# Ctrl_Joy.net
KiCad netlist of a schematic drawn in EAGLE
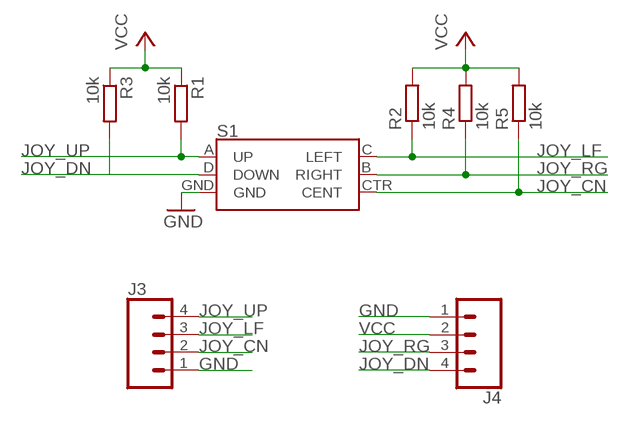
[diagram p0: schematic, sheet 1]

(export (version "E")
  (design (tool "Eeschema 10.0.6"))
  (components
    (comp (ref "J3")
      (value "CONN_04")
      (footprint "eagle-import:1X04")
      (libsource (lib "eagle-import") (part "CONN_04"))
    )
    (comp (ref "J4")
      (value "CONN_04")
      (footprint "eagle-import:1X04")
      (libsource (lib "eagle-import") (part "CONN_04"))
    )
    (comp (ref "R1")
      (value "10k")
      (footprint "eagle-import:R0603")
      (libsource (lib "eagle-import") (part "R-EU_R0603"))
    )
    (comp (ref "R2")
      (value "10k")
      (footprint "eagle-import:R0603")
      (libsource (lib "eagle-import") (part "R-EU_R0603"))
    )
    (comp (ref "R3")
      (value "10k")
      (footprint "eagle-import:R0603")
      (libsource (lib "eagle-import") (part "R-EU_R0603"))
    )
    (comp (ref "R4")
      (value "10k")
      (footprint "eagle-import:R0603")
      (libsource (lib "eagle-import") (part "R-EU_R0603"))
    )
    (comp (ref "R5")
      (value "10k")
      (footprint "eagle-import:R0603")
      (libsource (lib "eagle-import") (part "R-EU_R0603"))
    )
    (comp (ref "S1")
      (value "JOYSTICK_MINI")
      (footprint "eagle-import:JOYSTICK_MINI")
      (libsource (lib "eagle-import") (part "JOYSTICK_MINI"))
    )
  )
  (nets
    (net (code "1") (name "/JOY_CN") (class "Default")
      (node (ref "J3") (pin "2") (pinfunction "2_2") (pintype "passive"))
      (node (ref "R5") (pin "1") (pinfunction "1_1") (pintype "passive"))
      (node (ref "S1") (pin "CTR") (pinfunction "CENT_CTR") (pintype "bidirectional"))
    )
    (net (code "2") (name "/JOY_DN") (class "Default")
      (node (ref "J4") (pin "4") (pinfunction "4_4") (pintype "passive"))
      (node (ref "R3") (pin "2") (pinfunction "2_2") (pintype "passive"))
      (node (ref "S1") (pin "D") (pinfunction "DOWN_D") (pintype "bidirectional"))
    )
    (net (code "3") (name "/JOY_LF") (class "Default")
      (node (ref "J3") (pin "3") (pinfunction "3_3") (pintype "passive"))
      (node (ref "R2") (pin "1") (pinfunction "1_1") (pintype "passive"))
      (node (ref "S1") (pin "C") (pinfunction "LEFT_C") (pintype "bidirectional"))
    )
    (net (code "4") (name "/JOY_RG") (class "Default")
      (node (ref "J4") (pin "3") (pinfunction "3_3") (pintype "passive"))
      (node (ref "R4") (pin "1") (pinfunction "1_1") (pintype "passive"))
      (node (ref "S1") (pin "B") (pinfunction "RIGHT_B") (pintype "bidirectional"))
    )
    (net (code "5") (name "/JOY_UP") (class "Default")
      (node (ref "J3") (pin "4") (pinfunction "4_4") (pintype "passive"))
      (node (ref "R1") (pin "2") (pinfunction "2_2") (pintype "passive"))
      (node (ref "S1") (pin "A") (pinfunction "UP_A") (pintype "bidirectional"))
    )
    (net (code "6") (name "GND") (class "Default")
      (node (ref "J3") (pin "1") (pinfunction "1_1") (pintype "passive"))
      (node (ref "J4") (pin "1") (pinfunction "1_1") (pintype "passive"))
      (node (ref "S1") (pin "GND") (pinfunction "GND_GND") (pintype "bidirectional"))
    )
    (net (code "7") (name "VCC") (class "Default")
      (node (ref "J4") (pin "2") (pinfunction "2_2") (pintype "passive"))
      (node (ref "R1") (pin "1") (pinfunction "1_1") (pintype "passive"))
      (node (ref "R2") (pin "2") (pinfunction "2_2") (pintype "passive"))
      (node (ref "R3") (pin "1") (pinfunction "1_1") (pintype "passive"))
      (node (ref "R4") (pin "2") (pinfunction "2_2") (pintype "passive"))
      (node (ref "R5") (pin "2") (pinfunction "2_2") (pintype "passive"))
    )
  )
)
